# design.net
KiCad netlist of a schematic drawn in Altium Designer
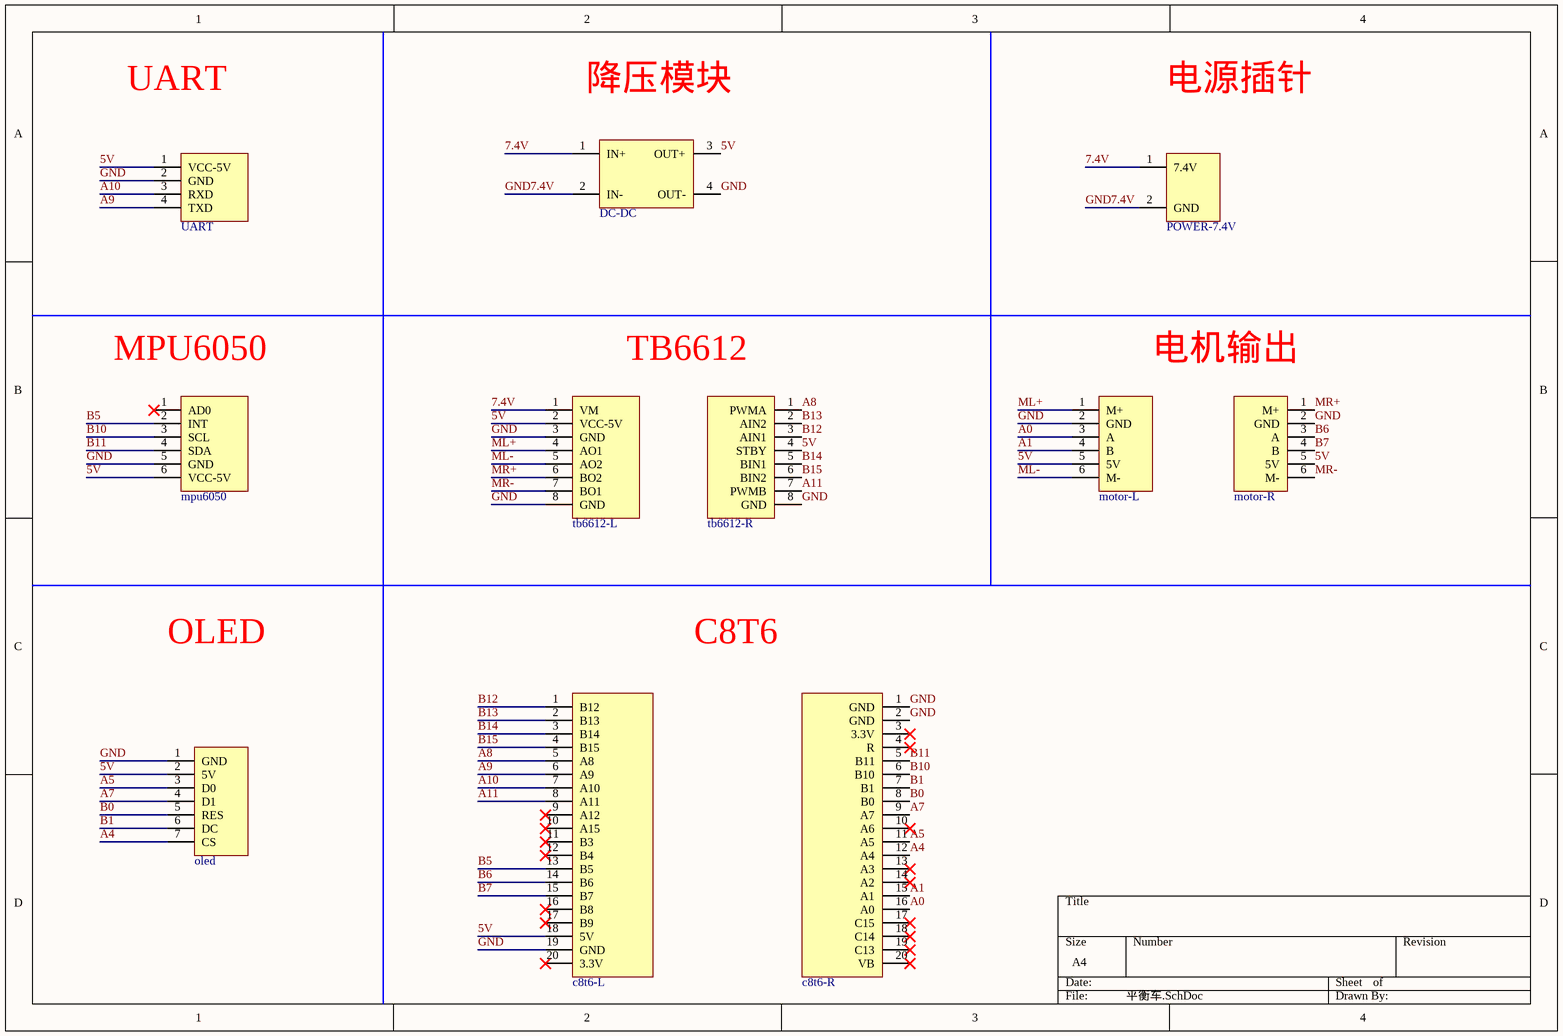
[diagram p0: 平衡车.SchDoc]

(export (version "E")
  (design (tool "Eeschema 10.0.6"))
  (components
    (comp (ref "c8t6-L")
      (value "c8t6-L")
      (footprint "HDR2.54-M-LI-20P")
      (libsource (lib "平衡车") (part "c8t6-L"))
    )
    (comp (ref "c8t6-R")
      (value "c8t6-R")
      (footprint "HDR2.54-M-LI-20P")
      (libsource (lib "平衡车") (part "c8t6-R"))
    )
    (comp (ref "DC-DC") (value "DC-DC") (footprint "DC-DC") (libsource (lib "平衡车") (part "DC-DC")))
    (comp (ref "motor-L")
      (value "motor-L")
      (footprint "HDR2.54-WI-6P")
      (libsource (lib "平衡车") (part "motor-L"))
    )
    (comp (ref "motor-R")
      (value "motor-R")
      (footprint "HDR2.54-WI-6P")
      (libsource (lib "平衡车") (part "motor-R"))
    )
    (comp (ref "mpu6050")
      (value "mpu6050")
      (footprint "HDR2.54-M-LI-6P")
      (libsource (lib "平衡车") (part "mpu6050"))
    )
    (comp (ref "oled") (value "oled") (footprint "HDR2.54-M-LI-7P") (libsource (lib "平衡车") (part "oled")))
    (comp (ref "POWER-7.4V")
      (value "POWER-7.4V")
      (footprint "HDR2.54-LI-2P")
      (libsource (lib "平衡车") (part "POWER-7.4V"))
    )
    (comp (ref "tb6612-L")
      (value "tb6612-L")
      (footprint "HDR2.54-M-LI-8P")
      (libsource (lib "平衡车") (part "tb6612-L"))
    )
    (comp (ref "tb6612-R")
      (value "tb6612-R")
      (footprint "HDR2.54-M-LI-8P")
      (libsource (lib "平衡车") (part "tb6612-R"))
    )
    (comp (ref "UART") (value "UART") (footprint "HDR2.54-M-LI-4P") (libsource (lib "平衡车") (part "UART")))
  )
  (nets
    (net (code "1") (name "/5V") (class "Default")
      (node (ref "DC-DC") (pin "3") (pinfunction "OUT+_3") (pintype "passive"))
      (node (ref "UART") (pin "1") (pinfunction "VCC-5V_1") (pintype "passive"))
      (node (ref "c8t6-L") (pin "18") (pinfunction "5V_18") (pintype "passive"))
      (node (ref "motor-L") (pin "5") (pinfunction "5V_5") (pintype "passive"))
      (node (ref "motor-R") (pin "5") (pinfunction "5V_5") (pintype "passive"))
      (node (ref "mpu6050") (pin "6") (pinfunction "VCC-5V_6") (pintype "passive"))
      (node (ref "oled") (pin "2") (pinfunction "5V_2") (pintype "passive"))
      (node (ref "tb6612-L") (pin "2") (pinfunction "VCC-5V_2") (pintype "passive"))
      (node (ref "tb6612-R") (pin "4") (pinfunction "STBY_4") (pintype "passive"))
    )
    (net (code "2") (name "/7.4V") (class "Default")
      (node (ref "DC-DC") (pin "1") (pinfunction "IN+_1") (pintype "passive"))
      (node (ref "POWER-7.4V") (pin "1") (pinfunction "7.4V_1") (pintype "passive"))
      (node (ref "tb6612-L") (pin "1") (pinfunction "VM_1") (pintype "passive"))
    )
    (net (code "3") (name "/A0") (class "Default")
      (node (ref "c8t6-R") (pin "16") (pinfunction "A0_16") (pintype "passive"))
      (node (ref "motor-L") (pin "3") (pinfunction "A_3") (pintype "passive"))
    )
    (net (code "4") (name "/A1") (class "Default")
      (node (ref "c8t6-R") (pin "15") (pinfunction "A1_15") (pintype "passive"))
      (node (ref "motor-L") (pin "4") (pinfunction "B_4") (pintype "passive"))
    )
    (net (code "5") (name "/A4") (class "Default")
      (node (ref "c8t6-R") (pin "12") (pinfunction "A4_12") (pintype "passive"))
      (node (ref "oled") (pin "7") (pinfunction "CS_7") (pintype "passive"))
    )
    (net (code "6") (name "/A5") (class "Default")
      (node (ref "c8t6-R") (pin "11") (pinfunction "A5_11") (pintype "passive"))
      (node (ref "oled") (pin "3") (pinfunction "D0_3") (pintype "passive"))
    )
    (net (code "7") (name "/A7") (class "Default")
      (node (ref "c8t6-R") (pin "9") (pinfunction "A7_9") (pintype "passive"))
      (node (ref "oled") (pin "4") (pinfunction "D1_4") (pintype "passive"))
    )
    (net (code "8") (name "/A8") (class "Default")
      (node (ref "c8t6-L") (pin "5") (pinfunction "A8_5") (pintype "passive"))
      (node (ref "tb6612-R") (pin "1") (pinfunction "PWMA_1") (pintype "passive"))
    )
    (net (code "9") (name "/A9") (class "Default")
      (node (ref "UART") (pin "4") (pinfunction "TXD_4") (pintype "passive"))
      (node (ref "c8t6-L") (pin "6") (pinfunction "A9_6") (pintype "passive"))
    )
    (net (code "10") (name "/A10") (class "Default")
      (node (ref "UART") (pin "3") (pinfunction "RXD_3") (pintype "passive"))
      (node (ref "c8t6-L") (pin "7") (pinfunction "A10_7") (pintype "passive"))
    )
    (net (code "11") (name "/A11") (class "Default")
      (node (ref "c8t6-L") (pin "8") (pinfunction "A11_8") (pintype "passive"))
      (node (ref "tb6612-R") (pin "7") (pinfunction "PWMB_7") (pintype "passive"))
    )
    (net (code "12") (name "/B0") (class "Default")
      (node (ref "c8t6-R") (pin "8") (pinfunction "B0_8") (pintype "passive"))
      (node (ref "oled") (pin "5") (pinfunction "RES_5") (pintype "passive"))
    )
    (net (code "13") (name "/B1") (class "Default")
      (node (ref "c8t6-R") (pin "7") (pinfunction "B1_7") (pintype "passive"))
      (node (ref "oled") (pin "6") (pinfunction "DC_6") (pintype "passive"))
    )
    (net (code "14") (name "/B5") (class "Default")
      (node (ref "c8t6-L") (pin "13") (pinfunction "B5_13") (pintype "passive"))
      (node (ref "mpu6050") (pin "2") (pinfunction "INT_2") (pintype "passive"))
    )
    (net (code "15") (name "/B6") (class "Default")
      (node (ref "c8t6-L") (pin "14") (pinfunction "B6_14") (pintype "passive"))
      (node (ref "motor-R") (pin "3") (pinfunction "A_3") (pintype "passive"))
    )
    (net (code "16") (name "/B7") (class "Default")
      (node (ref "c8t6-L") (pin "15") (pinfunction "B7_15") (pintype "passive"))
      (node (ref "motor-R") (pin "4") (pinfunction "B_4") (pintype "passive"))
    )
    (net (code "17") (name "/B10") (class "Default")
      (node (ref "c8t6-R") (pin "6") (pinfunction "B10_6") (pintype "passive"))
      (node (ref "mpu6050") (pin "3") (pinfunction "SCL_3") (pintype "passive"))
    )
    (net (code "18") (name "/B11") (class "Default")
      (node (ref "c8t6-R") (pin "5") (pinfunction "B11_5") (pintype "passive"))
      (node (ref "mpu6050") (pin "4") (pinfunction "SDA_4") (pintype "passive"))
    )
    (net (code "19") (name "/B12") (class "Default")
      (node (ref "c8t6-L") (pin "1") (pinfunction "B12_1") (pintype "passive"))
      (node (ref "tb6612-R") (pin "3") (pinfunction "AIN1_3") (pintype "passive"))
    )
    (net (code "20") (name "/B13") (class "Default")
      (node (ref "c8t6-L") (pin "2") (pinfunction "B13_2") (pintype "passive"))
      (node (ref "tb6612-R") (pin "2") (pinfunction "AIN2_2") (pintype "passive"))
    )
    (net (code "21") (name "/B14") (class "Default")
      (node (ref "c8t6-L") (pin "3") (pinfunction "B14_3") (pintype "passive"))
      (node (ref "tb6612-R") (pin "5") (pinfunction "BIN1_5") (pintype "passive"))
    )
    (net (code "22") (name "/B15") (class "Default")
      (node (ref "c8t6-L") (pin "4") (pinfunction "B15_4") (pintype "passive"))
      (node (ref "tb6612-R") (pin "6") (pinfunction "BIN2_6") (pintype "passive"))
    )
    (net (code "23") (name "/GND") (class "Default")
      (node (ref "DC-DC") (pin "4") (pinfunction "OUT-_4") (pintype "passive"))
      (node (ref "UART") (pin "2") (pinfunction "GND_2") (pintype "passive"))
      (node (ref "c8t6-L") (pin "19") (pinfunction "GND_19") (pintype "passive"))
      (node (ref "c8t6-R") (pin "1") (pinfunction "GND_1") (pintype "passive"))
      (node (ref "c8t6-R") (pin "2") (pinfunction "GND_2") (pintype "passive"))
      (node (ref "motor-L") (pin "2") (pinfunction "GND_2") (pintype "passive"))
      (node (ref "motor-R") (pin "2") (pinfunction "GND_2") (pintype "passive"))
      (node (ref "mpu6050") (pin "5") (pinfunction "GND_5") (pintype "passive"))
      (node (ref "oled") (pin "1") (pinfunction "GND_1") (pintype "passive"))
      (node (ref "tb6612-L") (pin "3") (pinfunction "GND_3") (pintype "passive"))
      (node (ref "tb6612-L") (pin "8") (pinfunction "GND_8") (pintype "passive"))
      (node (ref "tb6612-R") (pin "8") (pinfunction "GND_8") (pintype "passive"))
    )
    (net (code "24") (name "/GND7.4V") (class "Default")
      (node (ref "DC-DC") (pin "2") (pinfunction "IN-_2") (pintype "passive"))
      (node (ref "POWER-7.4V") (pin "2") (pinfunction "GND_2") (pintype "passive"))
    )
    (net (code "25") (name "/ML+") (class "Default")
      (node (ref "motor-L") (pin "1") (pinfunction "M+_1") (pintype "passive"))
      (node (ref "tb6612-L") (pin "4") (pinfunction "AO1_4") (pintype "passive"))
    )
    (net (code "26") (name "/ML-") (class "Default")
      (node (ref "motor-L") (pin "6") (pinfunction "M-_6") (pintype "passive"))
      (node (ref "tb6612-L") (pin "5") (pinfunction "AO2_5") (pintype "passive"))
    )
    (net (code "27") (name "/MR+") (class "Default")
      (node (ref "motor-R") (pin "1") (pinfunction "M+_1") (pintype "passive"))
      (node (ref "tb6612-L") (pin "6") (pinfunction "BO2_6") (pintype "passive"))
    )
    (net (code "28") (name "/MR-") (class "Default")
      (node (ref "motor-R") (pin "6") (pinfunction "M-_6") (pintype "passive"))
      (node (ref "tb6612-L") (pin "7") (pinfunction "BO1_7") (pintype "passive"))
    )
    (net (code "29") (name "unconnected-(c8t6-L-3.3V-Pad20)") (class "Default")
      (node (ref "c8t6-L") (pin "20") (pinfunction "3.3V_20") (pintype "passive+no_connect"))
    )
    (net (code "30") (name "unconnected-(c8t6-L-A12-Pad9)") (class "Default")
      (node (ref "c8t6-L") (pin "9") (pinfunction "A12_9") (pintype "passive+no_connect"))
    )
    (net (code "31") (name "unconnected-(c8t6-L-A15-Pad10)") (class "Default")
      (node (ref "c8t6-L") (pin "10") (pinfunction "A15_10") (pintype "passive+no_connect"))
    )
    (net (code "32") (name "unconnected-(c8t6-L-B3-Pad11)") (class "Default")
      (node (ref "c8t6-L") (pin "11") (pinfunction "B3_11") (pintype "passive+no_connect"))
    )
    (net (code "33") (name "unconnected-(c8t6-L-B4-Pad12)") (class "Default")
      (node (ref "c8t6-L") (pin "12") (pinfunction "B4_12") (pintype "passive+no_connect"))
    )
    (net (code "34") (name "unconnected-(c8t6-L-B8-Pad16)") (class "Default")
      (node (ref "c8t6-L") (pin "16") (pinfunction "B8_16") (pintype "passive+no_connect"))
    )
    (net (code "35") (name "unconnected-(c8t6-L-B9-Pad17)") (class "Default")
      (node (ref "c8t6-L") (pin "17") (pinfunction "B9_17") (pintype "passive+no_connect"))
    )
    (net (code "36") (name "unconnected-(c8t6-R-3.3V-Pad3)") (class "Default")
      (node (ref "c8t6-R") (pin "3") (pinfunction "3.3V_3") (pintype "passive+no_connect"))
    )
    (net (code "37") (name "unconnected-(c8t6-R-A2-Pad14)") (class "Default")
      (node (ref "c8t6-R") (pin "14") (pinfunction "A2_14") (pintype "passive+no_connect"))
    )
    (net (code "38") (name "unconnected-(c8t6-R-A3-Pad13)") (class "Default")
      (node (ref "c8t6-R") (pin "13") (pinfunction "A3_13") (pintype "passive+no_connect"))
    )
    (net (code "39") (name "unconnected-(c8t6-R-A6-Pad10)") (class "Default")
      (node (ref "c8t6-R") (pin "10") (pinfunction "A6_10") (pintype "passive+no_connect"))
    )
    (net (code "40") (name "unconnected-(c8t6-R-C13-Pad19)") (class "Default")
      (node (ref "c8t6-R") (pin "19") (pinfunction "C13_19") (pintype "passive+no_connect"))
    )
    (net (code "41") (name "unconnected-(c8t6-R-C14-Pad18)") (class "Default")
      (node (ref "c8t6-R") (pin "18") (pinfunction "C14_18") (pintype "passive+no_connect"))
    )
    (net (code "42") (name "unconnected-(c8t6-R-C15-Pad17)") (class "Default")
      (node (ref "c8t6-R") (pin "17") (pinfunction "C15_17") (pintype "passive+no_connect"))
    )
    (net (code "43") (name "unconnected-(c8t6-R-R-Pad4)") (class "Default")
      (node (ref "c8t6-R") (pin "4") (pinfunction "R_4") (pintype "passive+no_connect"))
    )
    (net (code "44") (name "unconnected-(c8t6-R-VB-Pad20)") (class "Default")
      (node (ref "c8t6-R") (pin "20") (pinfunction "VB_20") (pintype "passive+no_connect"))
    )
    (net (code "45") (name "unconnected-(mpu6050-AD0-Pad1)") (class "Default")
      (node (ref "mpu6050") (pin "1") (pinfunction "AD0_1") (pintype "passive+no_connect"))
    )
  )
)
